# additionneur.net
KiCad netlist of a schematic drawn in EAGLE
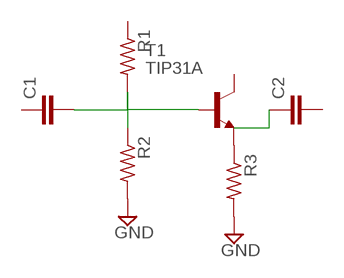
[diagram p0: schematic, sheet 1]

(export (version "E")
  (design (tool "Eeschema 10.0.6"))
  (components
    (comp (ref "C1")
      (value "C-EUC0603")
      (footprint "eagle-import:C0603")
      (libsource (lib "eagle-import") (part "C-EUC0603"))
    )
    (comp (ref "C2")
      (value "C-EUC0603")
      (footprint "eagle-import:C0603")
      (libsource (lib "eagle-import") (part "C-EUC0603"))
    )
    (comp (ref "R1")
      (value "R-US_R0603")
      (footprint "eagle-import:R0603")
      (libsource (lib "eagle-import") (part "R-US_R0603"))
    )
    (comp (ref "R2")
      (value "R-US_R0603")
      (footprint "eagle-import:R0603")
      (libsource (lib "eagle-import") (part "R-US_R0603"))
    )
    (comp (ref "R3")
      (value "R-US_R0603")
      (footprint "eagle-import:R0603")
      (libsource (lib "eagle-import") (part "R-US_R0603"))
    )
    (comp (ref "T1")
      (value "TIP31A")
      (footprint "eagle-import:TO220")
      (libsource (lib "eagle-import") (part "TIP31A"))
    )
  )
  (nets
    (net (code "1") (name "GND") (class "Default")
      (node (ref "R2") (pin "2") (pinfunction "2_2") (pintype "passive"))
      (node (ref "R3") (pin "2") (pinfunction "2_2") (pintype "passive"))
    )
    (net (code "2") (name "Net-(T1-B)") (class "Default")
      (node (ref "C1") (pin "2") (pinfunction "2_2") (pintype "passive"))
      (node (ref "R1") (pin "2") (pinfunction "2_2") (pintype "passive"))
      (node (ref "R2") (pin "1") (pinfunction "1_1") (pintype "passive"))
      (node (ref "T1") (pin "1") (pinfunction "B_1") (pintype "passive"))
    )
    (net (code "3") (name "Net-(T1-E)") (class "Default")
      (node (ref "R3") (pin "1") (pinfunction "1_1") (pintype "passive"))
      (node (ref "T1") (pin "3") (pinfunction "E_3") (pintype "passive"))
    )
    (net (code "4") (name "unconnected-(C1-Pad1)") (class "Default")
      (node (ref "C1") (pin "1") (pinfunction "1_1") (pintype "passive"))
    )
    (net (code "5") (name "unconnected-(C2-Pad1)") (class "Default")
      (node (ref "C2") (pin "1") (pinfunction "1_1") (pintype "passive"))
    )
    (net (code "6") (name "unconnected-(C2-Pad2)") (class "Default")
      (node (ref "C2") (pin "2") (pinfunction "2_2") (pintype "passive"))
    )
    (net (code "7") (name "unconnected-(R1-Pad1)") (class "Default")
      (node (ref "R1") (pin "1") (pinfunction "1_1") (pintype "passive"))
    )
    (net (code "8") (name "unconnected-(T1-C-Pad2)") (class "Default")
      (node (ref "T1") (pin "2") (pinfunction "C_2") (pintype "passive"))
    )
  )
)
